# untitled.net
KiCad netlist of a schematic drawn in EAGLE
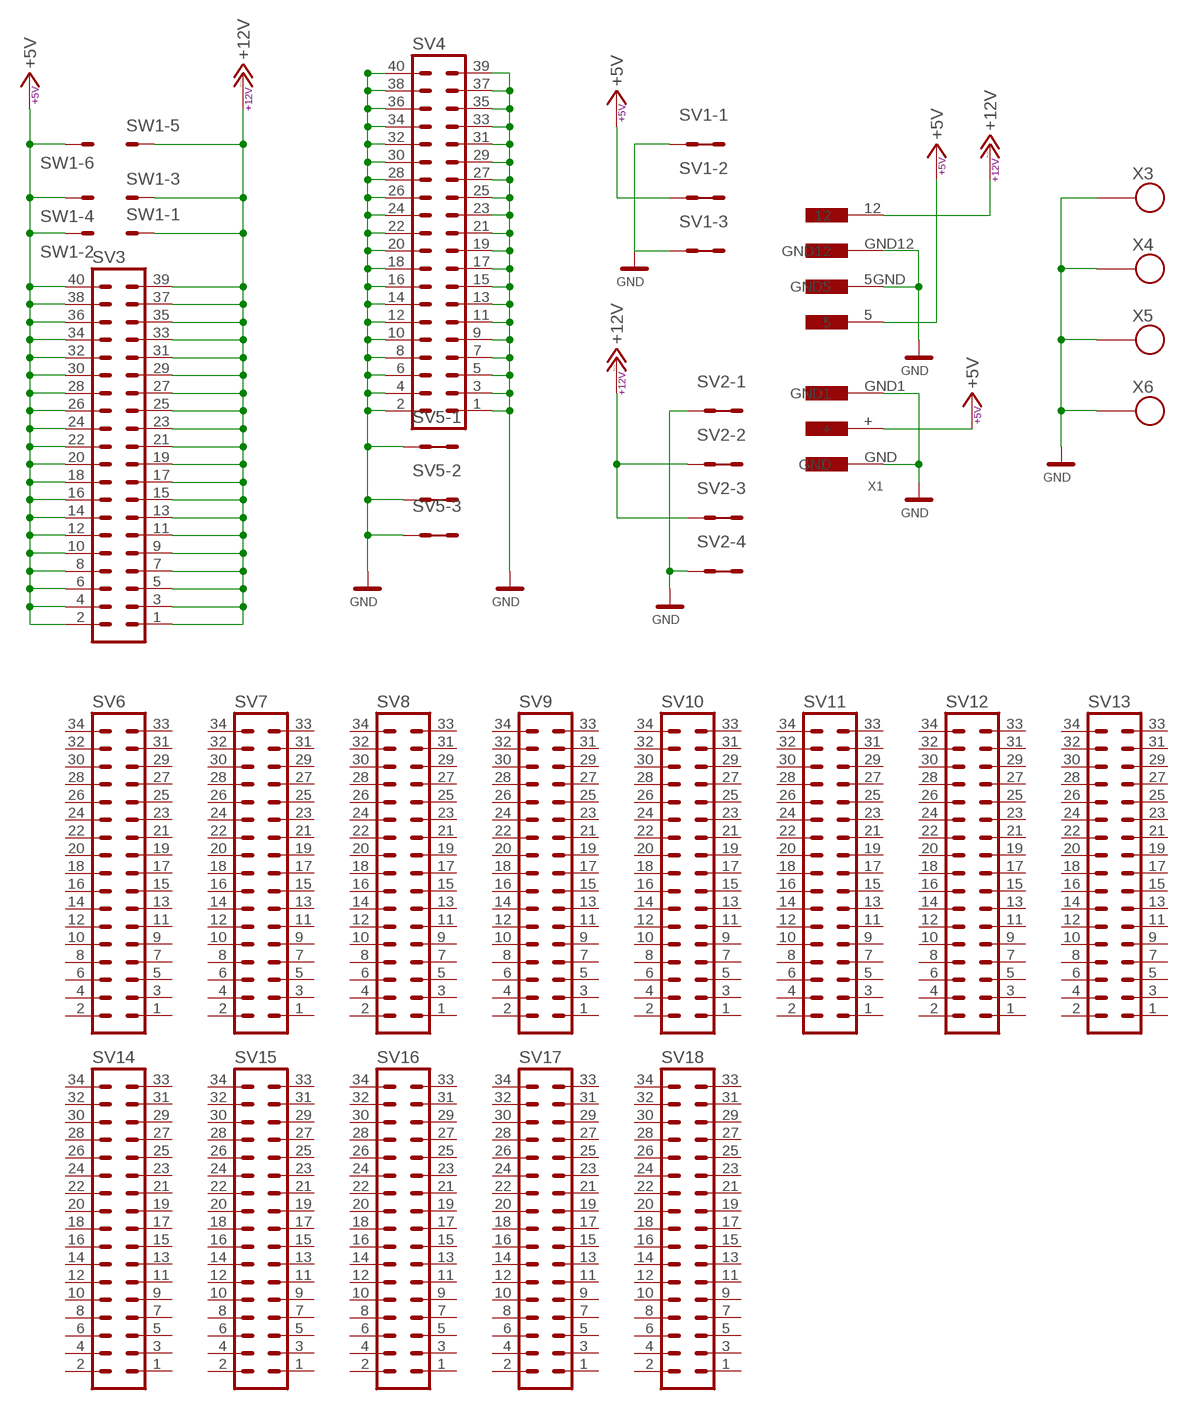
[diagram p0: schematic, sheet 1]

(export (version "E")
  (design (tool "Eeschema 10.0.6"))
  (components
    (comp (ref "SV1")
      (value "MA03-2")
      (footprint "eagle-import:MA03-2")
      (libsource (lib "eagle-import") (part "MA03-2"))
    )
    (comp (ref "SV2")
      (value "MA04-2")
      (footprint "eagle-import:MA04-2")
      (libsource (lib "eagle-import") (part "MA04-2"))
    )
    (comp (ref "SV3")
      (value "MA20-2")
      (footprint "eagle-import:MA20-2")
      (libsource (lib "eagle-import") (part "MA20-2"))
    )
    (comp (ref "SV4")
      (value "MA20-2")
      (footprint "eagle-import:MA20-2")
      (fields (field (name "OC_FARNELL") "unknown") (field (name "OC_NEWARK") "unknown"))
      (libsource (lib "eagle-import") (part "MA20-2"))
    )
    (comp (ref "SV5")
      (value "MA03-2")
      (footprint "eagle-import:MA03-2")
      (libsource (lib "eagle-import") (part "MA03-2"))
    )
    (comp (ref "SV6")
      (value "MA17-2")
      (footprint "eagle-import:MA17-2")
      (libsource (lib "eagle-import") (part "MA17-2"))
    )
    (comp (ref "SV7")
      (value "MA17-2")
      (footprint "eagle-import:MA17-2")
      (libsource (lib "eagle-import") (part "MA17-2"))
    )
    (comp (ref "SV8")
      (value "MA17-2")
      (footprint "eagle-import:MA17-2")
      (libsource (lib "eagle-import") (part "MA17-2"))
    )
    (comp (ref "SV9")
      (value "MA17-2")
      (footprint "eagle-import:MA17-2")
      (libsource (lib "eagle-import") (part "MA17-2"))
    )
    (comp (ref "SV10")
      (value "MA17-2")
      (footprint "eagle-import:MA17-2")
      (libsource (lib "eagle-import") (part "MA17-2"))
    )
    (comp (ref "SV11")
      (value "MA17-2")
      (footprint "eagle-import:MA17-2")
      (libsource (lib "eagle-import") (part "MA17-2"))
    )
    (comp (ref "SV12")
      (value "MA17-2")
      (footprint "eagle-import:MA17-2")
      (libsource (lib "eagle-import") (part "MA17-2"))
    )
    (comp (ref "SV13")
      (value "MA17-2")
      (footprint "eagle-import:MA17-2")
      (libsource (lib "eagle-import") (part "MA17-2"))
    )
    (comp (ref "SV14")
      (value "MA17-2")
      (footprint "eagle-import:MA17-2")
      (libsource (lib "eagle-import") (part "MA17-2"))
    )
    (comp (ref "SV15")
      (value "MA17-2")
      (footprint "eagle-import:MA17-2")
      (fields (field (name "OC_FARNELL") "unknown") (field (name "OC_NEWARK") "unknown"))
      (libsource (lib "eagle-import") (part "MA17-2"))
    )
    (comp (ref "SV16")
      (value "MA17-2")
      (footprint "eagle-import:MA17-2")
      (fields (field (name "OC_FARNELL") "unknown") (field (name "OC_NEWARK") "unknown"))
      (libsource (lib "eagle-import") (part "MA17-2"))
    )
    (comp (ref "SV17")
      (value "MA17-2")
      (footprint "eagle-import:MA17-2")
      (fields (field (name "OC_FARNELL") "unknown") (field (name "OC_NEWARK") "unknown"))
      (libsource (lib "eagle-import") (part "MA17-2"))
    )
    (comp (ref "SV18")
      (value "MA17-2")
      (footprint "eagle-import:MA17-2")
      (fields (field (name "OC_FARNELL") "unknown") (field (name "OC_NEWARK") "unknown"))
      (libsource (lib "eagle-import") (part "MA17-2"))
    )
    (comp (ref "SW1")
      (value "MA03-3")
      (footprint "eagle-import:MA03-2")
      (libsource (lib "eagle-import") (part "MA03-3"))
    )
    (comp (ref "X1")
      (value "KONEKTOR_DC_2.1MM")
      (footprint "eagle-import:KONEKTOR_DC_2.1MM")
      (libsource (lib "eagle-import") (part "KONEKTOR_DC_2.1MM"))
    )
    (comp (ref "X2")
      (value "POWER_HDD")
      (footprint "eagle-import:POWER_HDD")
      (libsource (lib "eagle-import") (part "POWER_HDD"))
    )
    (comp (ref "X3")
      (value "SROUB3M")
      (footprint "eagle-import:SROUB3M")
      (libsource (lib "eagle-import") (part "SROUB3M"))
    )
    (comp (ref "X4")
      (value "SROUB3M")
      (footprint "eagle-import:SROUB3M")
      (libsource (lib "eagle-import") (part "SROUB3M"))
    )
    (comp (ref "X5")
      (value "SROUB3M")
      (footprint "eagle-import:SROUB3M")
      (libsource (lib "eagle-import") (part "SROUB3M"))
    )
    (comp (ref "X6")
      (value "SROUB3M")
      (footprint "eagle-import:SROUB3M")
      (libsource (lib "eagle-import") (part "SROUB3M"))
    )
  )
  (nets
    (net (code "1") (name "+5V") (class "Default")
      (node (ref "SV1") (pin "3") (pinfunction "K_3") (pintype "passive"))
      (node (ref "SV1") (pin "4") (pinfunction "K_4") (pintype "passive"))
      (node (ref "SV3") (pin "10") (pinfunction "10_10") (pintype "passive"))
      (node (ref "SV3") (pin "12") (pinfunction "12_12") (pintype "passive"))
      (node (ref "SV3") (pin "14") (pinfunction "14_14") (pintype "passive"))
      (node (ref "SV3") (pin "16") (pinfunction "16_16") (pintype "passive"))
      (node (ref "SV3") (pin "18") (pinfunction "18_18") (pintype "passive"))
      (node (ref "SV3") (pin "2") (pinfunction "2_2") (pintype "passive"))
      (node (ref "SV3") (pin "20") (pinfunction "20_20") (pintype "passive"))
      (node (ref "SV3") (pin "22") (pinfunction "22_22") (pintype "passive"))
      (node (ref "SV3") (pin "24") (pinfunction "24_24") (pintype "passive"))
      (node (ref "SV3") (pin "26") (pinfunction "26_26") (pintype "passive"))
      (node (ref "SV3") (pin "28") (pinfunction "28_28") (pintype "passive"))
      (node (ref "SV3") (pin "30") (pinfunction "30_30") (pintype "passive"))
      (node (ref "SV3") (pin "32") (pinfunction "32_32") (pintype "passive"))
      (node (ref "SV3") (pin "34") (pinfunction "34_34") (pintype "passive"))
      (node (ref "SV3") (pin "36") (pinfunction "36_36") (pintype "passive"))
      (node (ref "SV3") (pin "38") (pinfunction "38_38") (pintype "passive"))
      (node (ref "SV3") (pin "4") (pinfunction "4_4") (pintype "passive"))
      (node (ref "SV3") (pin "40") (pinfunction "40_40") (pintype "passive"))
      (node (ref "SV3") (pin "6") (pinfunction "6_6") (pintype "passive"))
      (node (ref "SV3") (pin "8") (pinfunction "8_8") (pintype "passive"))
      (node (ref "SW1") (pin "2") (pinfunction "P$1_2") (pintype "passive"))
      (node (ref "SW1") (pin "4") (pinfunction "P$1_4") (pintype "passive"))
      (node (ref "SW1") (pin "6") (pinfunction "P$1_6") (pintype "passive"))
      (node (ref "X1") (pin "+") (pinfunction "+_+") (pintype "bidirectional"))
      (node (ref "X2") (pin "5") (pinfunction "5_5") (pintype "passive"))
    )
    (net (code "2") (name "+12V") (class "Default")
      (node (ref "SV2") (pin "3") (pinfunction "K_3") (pintype "passive"))
      (node (ref "SV2") (pin "4") (pinfunction "K_4") (pintype "passive"))
      (node (ref "SV2") (pin "5") (pinfunction "K_5") (pintype "passive"))
      (node (ref "SV2") (pin "6") (pinfunction "K_6") (pintype "passive"))
      (node (ref "SV3") (pin "1") (pinfunction "1_1") (pintype "passive"))
      (node (ref "SV3") (pin "11") (pinfunction "11_11") (pintype "passive"))
      (node (ref "SV3") (pin "13") (pinfunction "13_13") (pintype "passive"))
      (node (ref "SV3") (pin "15") (pinfunction "15_15") (pintype "passive"))
      (node (ref "SV3") (pin "17") (pinfunction "17_17") (pintype "passive"))
      (node (ref "SV3") (pin "19") (pinfunction "19_19") (pintype "passive"))
      (node (ref "SV3") (pin "21") (pinfunction "21_21") (pintype "passive"))
      (node (ref "SV3") (pin "23") (pinfunction "23_23") (pintype "passive"))
      (node (ref "SV3") (pin "25") (pinfunction "25_25") (pintype "passive"))
      (node (ref "SV3") (pin "27") (pinfunction "27_27") (pintype "passive"))
      (node (ref "SV3") (pin "29") (pinfunction "29_29") (pintype "passive"))
      (node (ref "SV3") (pin "3") (pinfunction "3_3") (pintype "passive"))
      (node (ref "SV3") (pin "31") (pinfunction "31_31") (pintype "passive"))
      (node (ref "SV3") (pin "33") (pinfunction "33_33") (pintype "passive"))
      (node (ref "SV3") (pin "35") (pinfunction "35_35") (pintype "passive"))
      (node (ref "SV3") (pin "37") (pinfunction "37_37") (pintype "passive"))
      (node (ref "SV3") (pin "39") (pinfunction "39_39") (pintype "passive"))
      (node (ref "SV3") (pin "5") (pinfunction "5_5") (pintype "passive"))
      (node (ref "SV3") (pin "7") (pinfunction "7_7") (pintype "passive"))
      (node (ref "SV3") (pin "9") (pinfunction "9_9") (pintype "passive"))
      (node (ref "SW1") (pin "1") (pinfunction "P$1_1") (pintype "passive"))
      (node (ref "SW1") (pin "3") (pinfunction "P$1_3") (pintype "passive"))
      (node (ref "SW1") (pin "5") (pinfunction "P$1_5") (pintype "passive"))
      (node (ref "X2") (pin "12") (pinfunction "12_12") (pintype "passive"))
    )
    (net (code "3") (name "GND") (class "Default")
      (node (ref "SV1") (pin "1") (pinfunction "K_1") (pintype "passive"))
      (node (ref "SV1") (pin "2") (pinfunction "K_2") (pintype "passive"))
      (node (ref "SV1") (pin "5") (pinfunction "K_5") (pintype "passive"))
      (node (ref "SV1") (pin "6") (pinfunction "K_6") (pintype "passive"))
      (node (ref "SV2") (pin "1") (pinfunction "K_1") (pintype "passive"))
      (node (ref "SV2") (pin "2") (pinfunction "K_2") (pintype "passive"))
      (node (ref "SV2") (pin "7") (pinfunction "K_7") (pintype "passive"))
      (node (ref "SV2") (pin "8") (pinfunction "K_8") (pintype "passive"))
      (node (ref "SV4") (pin "1") (pinfunction "1_1") (pintype "passive"))
      (node (ref "SV4") (pin "10") (pinfunction "10_10") (pintype "passive"))
      (node (ref "SV4") (pin "11") (pinfunction "11_11") (pintype "passive"))
      (node (ref "SV4") (pin "12") (pinfunction "12_12") (pintype "passive"))
      (node (ref "SV4") (pin "13") (pinfunction "13_13") (pintype "passive"))
      (node (ref "SV4") (pin "14") (pinfunction "14_14") (pintype "passive"))
      (node (ref "SV4") (pin "15") (pinfunction "15_15") (pintype "passive"))
      (node (ref "SV4") (pin "16") (pinfunction "16_16") (pintype "passive"))
      (node (ref "SV4") (pin "17") (pinfunction "17_17") (pintype "passive"))
      (node (ref "SV4") (pin "18") (pinfunction "18_18") (pintype "passive"))
      (node (ref "SV4") (pin "19") (pinfunction "19_19") (pintype "passive"))
      (node (ref "SV4") (pin "2") (pinfunction "2_2") (pintype "passive"))
      (node (ref "SV4") (pin "20") (pinfunction "20_20") (pintype "passive"))
      (node (ref "SV4") (pin "21") (pinfunction "21_21") (pintype "passive"))
      (node (ref "SV4") (pin "22") (pinfunction "22_22") (pintype "passive"))
      (node (ref "SV4") (pin "23") (pinfunction "23_23") (pintype "passive"))
      (node (ref "SV4") (pin "24") (pinfunction "24_24") (pintype "passive"))
      (node (ref "SV4") (pin "25") (pinfunction "25_25") (pintype "passive"))
      (node (ref "SV4") (pin "26") (pinfunction "26_26") (pintype "passive"))
      (node (ref "SV4") (pin "27") (pinfunction "27_27") (pintype "passive"))
      (node (ref "SV4") (pin "28") (pinfunction "28_28") (pintype "passive"))
      (node (ref "SV4") (pin "29") (pinfunction "29_29") (pintype "passive"))
      (node (ref "SV4") (pin "3") (pinfunction "3_3") (pintype "passive"))
      (node (ref "SV4") (pin "30") (pinfunction "30_30") (pintype "passive"))
      (node (ref "SV4") (pin "31") (pinfunction "31_31") (pintype "passive"))
      (node (ref "SV4") (pin "32") (pinfunction "32_32") (pintype "passive"))
      (node (ref "SV4") (pin "33") (pinfunction "33_33") (pintype "passive"))
      (node (ref "SV4") (pin "34") (pinfunction "34_34") (pintype "passive"))
      (node (ref "SV4") (pin "35") (pinfunction "35_35") (pintype "passive"))
      (node (ref "SV4") (pin "36") (pinfunction "36_36") (pintype "passive"))
      (node (ref "SV4") (pin "37") (pinfunction "37_37") (pintype "passive"))
      (node (ref "SV4") (pin "38") (pinfunction "38_38") (pintype "passive"))
      (node (ref "SV4") (pin "39") (pinfunction "39_39") (pintype "passive"))
      (node (ref "SV4") (pin "4") (pinfunction "4_4") (pintype "passive"))
      (node (ref "SV4") (pin "40") (pinfunction "40_40") (pintype "passive"))
      (node (ref "SV4") (pin "5") (pinfunction "5_5") (pintype "passive"))
      (node (ref "SV4") (pin "6") (pinfunction "6_6") (pintype "passive"))
      (node (ref "SV4") (pin "7") (pinfunction "7_7") (pintype "passive"))
      (node (ref "SV4") (pin "8") (pinfunction "8_8") (pintype "passive"))
      (node (ref "SV4") (pin "9") (pinfunction "9_9") (pintype "passive"))
      (node (ref "SV5") (pin "1") (pinfunction "K_1") (pintype "passive"))
      (node (ref "SV5") (pin "2") (pinfunction "K_2") (pintype "passive"))
      (node (ref "SV5") (pin "3") (pinfunction "K_3") (pintype "passive"))
      (node (ref "SV5") (pin "4") (pinfunction "K_4") (pintype "passive"))
      (node (ref "SV5") (pin "5") (pinfunction "K_5") (pintype "passive"))
      (node (ref "SV5") (pin "6") (pinfunction "K_6") (pintype "passive"))
      (node (ref "X1") (pin "GND") (pinfunction "GND_GND") (pintype "bidirectional"))
      (node (ref "X1") (pin "GND1") (pinfunction "GND1_GND1") (pintype "bidirectional"))
      (node (ref "X2") (pin "5GND") (pinfunction "GND5_5GND") (pintype "passive"))
      (node (ref "X2") (pin "GND12") (pinfunction "GND12_GND12") (pintype "passive"))
      (node (ref "X3") (pin "P$1") (pinfunction "P$1_P$1") (pintype "bidirectional"))
      (node (ref "X4") (pin "P$1") (pinfunction "P$1_P$1") (pintype "bidirectional"))
      (node (ref "X5") (pin "P$1") (pinfunction "P$1_P$1") (pintype "bidirectional"))
      (node (ref "X6") (pin "P$1") (pinfunction "P$1_P$1") (pintype "bidirectional"))
    )
    (net (code "4") (name "unconnected-(SV6-Pad1)") (class "Default")
      (node (ref "SV6") (pin "1") (pinfunction "1_1") (pintype "passive"))
    )
    (net (code "5") (name "unconnected-(SV6-Pad2)") (class "Default")
      (node (ref "SV6") (pin "2") (pinfunction "2_2") (pintype "passive"))
    )
    (net (code "6") (name "unconnected-(SV6-Pad3)") (class "Default")
      (node (ref "SV6") (pin "3") (pinfunction "3_3") (pintype "passive"))
    )
    (net (code "7") (name "unconnected-(SV6-Pad4)") (class "Default")
      (node (ref "SV6") (pin "4") (pinfunction "4_4") (pintype "passive"))
    )
    (net (code "8") (name "unconnected-(SV6-Pad5)") (class "Default")
      (node (ref "SV6") (pin "5") (pinfunction "5_5") (pintype "passive"))
    )
    (net (code "9") (name "unconnected-(SV6-Pad6)") (class "Default")
      (node (ref "SV6") (pin "6") (pinfunction "6_6") (pintype "passive"))
    )
    (net (code "10") (name "unconnected-(SV6-Pad7)") (class "Default")
      (node (ref "SV6") (pin "7") (pinfunction "7_7") (pintype "passive"))
    )
    (net (code "11") (name "unconnected-(SV6-Pad8)") (class "Default")
      (node (ref "SV6") (pin "8") (pinfunction "8_8") (pintype "passive"))
    )
    (net (code "12") (name "unconnected-(SV6-Pad9)") (class "Default")
      (node (ref "SV6") (pin "9") (pinfunction "9_9") (pintype "passive"))
    )
    (net (code "13") (name "unconnected-(SV6-Pad10)") (class "Default")
      (node (ref "SV6") (pin "10") (pinfunction "10_10") (pintype "passive"))
    )
    (net (code "14") (name "unconnected-(SV6-Pad11)") (class "Default")
      (node (ref "SV6") (pin "11") (pinfunction "11_11") (pintype "passive"))
    )
    (net (code "15") (name "unconnected-(SV6-Pad12)") (class "Default")
      (node (ref "SV6") (pin "12") (pinfunction "12_12") (pintype "passive"))
    )
    (net (code "16") (name "unconnected-(SV6-Pad13)") (class "Default")
      (node (ref "SV6") (pin "13") (pinfunction "13_13") (pintype "passive"))
    )
    (net (code "17") (name "unconnected-(SV6-Pad14)") (class "Default")
      (node (ref "SV6") (pin "14") (pinfunction "14_14") (pintype "passive"))
    )
    (net (code "18") (name "unconnected-(SV6-Pad15)") (class "Default")
      (node (ref "SV6") (pin "15") (pinfunction "15_15") (pintype "passive"))
    )
    (net (code "19") (name "unconnected-(SV6-Pad16)") (class "Default")
      (node (ref "SV6") (pin "16") (pinfunction "16_16") (pintype "passive"))
    )
    (net (code "20") (name "unconnected-(SV6-Pad17)") (class "Default")
      (node (ref "SV6") (pin "17") (pinfunction "17_17") (pintype "passive"))
    )
    (net (code "21") (name "unconnected-(SV6-Pad18)") (class "Default")
      (node (ref "SV6") (pin "18") (pinfunction "18_18") (pintype "passive"))
    )
    (net (code "22") (name "unconnected-(SV6-Pad19)") (class "Default")
      (node (ref "SV6") (pin "19") (pinfunction "19_19") (pintype "passive"))
    )
    (net (code "23") (name "unconnected-(SV6-Pad20)") (class "Default")
      (node (ref "SV6") (pin "20") (pinfunction "20_20") (pintype "passive"))
    )
    (net (code "24") (name "unconnected-(SV6-Pad21)") (class "Default")
      (node (ref "SV6") (pin "21") (pinfunction "21_21") (pintype "passive"))
    )
    (net (code "25") (name "unconnected-(SV6-Pad22)") (class "Default")
      (node (ref "SV6") (pin "22") (pinfunction "22_22") (pintype "passive"))
    )
    (net (code "26") (name "unconnected-(SV6-Pad23)") (class "Default")
      (node (ref "SV6") (pin "23") (pinfunction "23_23") (pintype "passive"))
    )
    (net (code "27") (name "unconnected-(SV6-Pad24)") (class "Default")
      (node (ref "SV6") (pin "24") (pinfunction "24_24") (pintype "passive"))
    )
    (net (code "28") (name "unconnected-(SV6-Pad25)") (class "Default")
      (node (ref "SV6") (pin "25") (pinfunction "25_25") (pintype "passive"))
    )
    (net (code "29") (name "unconnected-(SV6-Pad26)") (class "Default")
      (node (ref "SV6") (pin "26") (pinfunction "26_26") (pintype "passive"))
    )
    (net (code "30") (name "unconnected-(SV6-Pad27)") (class "Default")
      (node (ref "SV6") (pin "27") (pinfunction "27_27") (pintype "passive"))
    )
    (net (code "31") (name "unconnected-(SV6-Pad28)") (class "Default")
      (node (ref "SV6") (pin "28") (pinfunction "28_28") (pintype "passive"))
    )
    (net (code "32") (name "unconnected-(SV6-Pad29)") (class "Default")
      (node (ref "SV6") (pin "29") (pinfunction "29_29") (pintype "passive"))
    )
    (net (code "33") (name "unconnected-(SV6-Pad30)") (class "Default")
      (node (ref "SV6") (pin "30") (pinfunction "30_30") (pintype "passive"))
    )
    (net (code "34") (name "unconnected-(SV6-Pad31)") (class "Default")
      (node (ref "SV6") (pin "31") (pinfunction "31_31") (pintype "passive"))
    )
    (net (code "35") (name "unconnected-(SV6-Pad32)") (class "Default")
      (node (ref "SV6") (pin "32") (pinfunction "32_32") (pintype "passive"))
    )
    (net (code "36") (name "unconnected-(SV6-Pad33)") (class "Default")
      (node (ref "SV6") (pin "33") (pinfunction "33_33") (pintype "passive"))
    )
    (net (code "37") (name "unconnected-(SV6-Pad34)") (class "Default")
      (node (ref "SV6") (pin "34") (pinfunction "34_34") (pintype "passive"))
    )
    (net (code "38") (name "unconnected-(SV7-Pad1)") (class "Default")
      (node (ref "SV7") (pin "1") (pinfunction "1_1") (pintype "passive"))
    )
    (net (code "39") (name "unconnected-(SV7-Pad2)") (class "Default")
      (node (ref "SV7") (pin "2") (pinfunction "2_2") (pintype "passive"))
    )
    (net (code "40") (name "unconnected-(SV7-Pad3)") (class "Default")
      (node (ref "SV7") (pin "3") (pinfunction "3_3") (pintype "passive"))
    )
    (net (code "41") (name "unconnected-(SV7-Pad4)") (class "Default")
      (node (ref "SV7") (pin "4") (pinfunction "4_4") (pintype "passive"))
    )
    (net (code "42") (name "unconnected-(SV7-Pad5)") (class "Default")
      (node (ref "SV7") (pin "5") (pinfunction "5_5") (pintype "passive"))
    )
    (net (code "43") (name "unconnected-(SV7-Pad6)") (class "Default")
      (node (ref "SV7") (pin "6") (pinfunction "6_6") (pintype "passive"))
    )
    (net (code "44") (name "unconnected-(SV7-Pad7)") (class "Default")
      (node (ref "SV7") (pin "7") (pinfunction "7_7") (pintype "passive"))
    )
    (net (code "45") (name "unconnected-(SV7-Pad8)") (class "Default")
      (node (ref "SV7") (pin "8") (pinfunction "8_8") (pintype "passive"))
    )
    (net (code "46") (name "unconnected-(SV7-Pad9)") (class "Default")
      (node (ref "SV7") (pin "9") (pinfunction "9_9") (pintype "passive"))
    )
    (net (code "47") (name "unconnected-(SV7-Pad10)") (class "Default")
      (node (ref "SV7") (pin "10") (pinfunction "10_10") (pintype "passive"))
    )
    (net (code "48") (name "unconnected-(SV7-Pad11)") (class "Default")
      (node (ref "SV7") (pin "11") (pinfunction "11_11") (pintype "passive"))
    )
    (net (code "49") (name "unconnected-(SV7-Pad12)") (class "Default")
      (node (ref "SV7") (pin "12") (pinfunction "12_12") (pintype "passive"))
    )
    (net (code "50") (name "unconnected-(SV7-Pad13)") (class "Default")
      (node (ref "SV7") (pin "13") (pinfunction "13_13") (pintype "passive"))
    )
    (net (code "51") (name "unconnected-(SV7-Pad14)") (class "Default")
      (node (ref "SV7") (pin "14") (pinfunction "14_14") (pintype "passive"))
    )
    (net (code "52") (name "unconnected-(SV7-Pad15)") (class "Default")
      (node (ref "SV7") (pin "15") (pinfunction "15_15") (pintype "passive"))
    )
    (net (code "53") (name "unconnected-(SV7-Pad16)") (class "Default")
      (node (ref "SV7") (pin "16") (pinfunction "16_16") (pintype "passive"))
    )
    (net (code "54") (name "unconnected-(SV7-Pad17)") (class "Default")
      (node (ref "SV7") (pin "17") (pinfunction "17_17") (pintype "passive"))
    )
    (net (code "55") (name "unconnected-(SV7-Pad18)") (class "Default")
      (node (ref "SV7") (pin "18") (pinfunction "18_18") (pintype "passive"))
    )
    (net (code "56") (name "unconnected-(SV7-Pad19)") (class "Default")
      (node (ref "SV7") (pin "19") (pinfunction "19_19") (pintype "passive"))
    )
    (net (code "57") (name "unconnected-(SV7-Pad20)") (class "Default")
      (node (ref "SV7") (pin "20") (pinfunction "20_20") (pintype "passive"))
    )
    (net (code "58") (name "unconnected-(SV7-Pad21)") (class "Default")
      (node (ref "SV7") (pin "21") (pinfunction "21_21") (pintype "passive"))
    )
    (net (code "59") (name "unconnected-(SV7-Pad22)") (class "Default")
      (node (ref "SV7") (pin "22") (pinfunction "22_22") (pintype "passive"))
    )
    (net (code "60") (name "unconnected-(SV7-Pad23)") (class "Default")
      (node (ref "SV7") (pin "23") (pinfunction "23_23") (pintype "passive"))
    )
    (net (code "61") (name "unconnected-(SV7-Pad24)") (class "Default")
      (node (ref "SV7") (pin "24") (pinfunction "24_24") (pintype "passive"))
    )
    (net (code "62") (name "unconnected-(SV7-Pad25)") (class "Default")
      (node (ref "SV7") (pin "25") (pinfunction "25_25") (pintype "passive"))
    )
    (net (code "63") (name "unconnected-(SV7-Pad26)") (class "Default")
      (node (ref "SV7") (pin "26") (pinfunction "26_26") (pintype "passive"))
    )
    (net (code "64") (name "unconnected-(SV7-Pad27)") (class "Default")
      (node (ref "SV7") (pin "27") (pinfunction "27_27") (pintype "passive"))
    )
    (net (code "65") (name "unconnected-(SV7-Pad28)") (class "Default")
      (node (ref "SV7") (pin "28") (pinfunction "28_28") (pintype "passive"))
    )
    (net (code "66") (name "unconnected-(SV7-Pad29)") (class "Default")
      (node (ref "SV7") (pin "29") (pinfunction "29_29") (pintype "passive"))
    )
    (net (code "67") (name "unconnected-(SV7-Pad30)") (class "Default")
      (node (ref "SV7") (pin "30") (pinfunction "30_30") (pintype "passive"))
    )
    (net (code "68") (name "unconnected-(SV7-Pad31)") (class "Default")
      (node (ref "SV7") (pin "31") (pinfunction "31_31") (pintype "passive"))
    )
    (net (code "69") (name "unconnected-(SV7-Pad32)") (class "Default")
      (node (ref "SV7") (pin "32") (pinfunction "32_32") (pintype "passive"))
    )
    (net (code "70") (name "unconnected-(SV7-Pad33)") (class "Default")
      (node (ref "SV7") (pin "33") (pinfunction "33_33") (pintype "passive"))
    )
    (net (code "71") (name "unconnected-(SV7-Pad34)") (class "Default")
      (node (ref "SV7") (pin "34") (pinfunction "34_34") (pintype "passive"))
    )
    (net (code "72") (name "unconnected-(SV8-Pad1)") (class "Default")
      (node (ref "SV8") (pin "1") (pinfunction "1_1") (pintype "passive"))
    )
    (net (code "73") (name "unconnected-(SV8-Pad2)") (class "Default")
      (node (ref "SV8") (pin "2") (pinfunction "2_2") (pintype "passive"))
    )
    (net (code "74") (name "unconnected-(SV8-Pad3)") (class "Default")
      (node (ref "SV8") (pin "3") (pinfunction "3_3") (pintype "passive"))
    )
    (net (code "75") (name "unconnected-(SV8-Pad4)") (class "Default")
      (node (ref "SV8") (pin "4") (pinfunction "4_4") (pintype "passive"))
    )
    (net (code "76") (name "unconnected-(SV8-Pad5)") (class "Default")
      (node (ref "SV8") (pin "5") (pinfunction "5_5") (pintype "passive"))
    )
    (net (code "77") (name "unconnected-(SV8-Pad6)") (class "Default")
      (node (ref "SV8") (pin "6") (pinfunction "6_6") (pintype "passive"))
    )
    (net (code "78") (name "unconnected-(SV8-Pad7)") (class "Default")
      (node (ref "SV8") (pin "7") (pinfunction "7_7") (pintype "passive"))
    )
    (net (code "79") (name "unconnected-(SV8-Pad8)") (class "Default")
      (node (ref "SV8") (pin "8") (pinfunction "8_8") (pintype "passive"))
    )
    (net (code "80") (name "unconnected-(SV8-Pad9)") (class "Default")
      (node (ref "SV8") (pin "9") (pinfunction "9_9") (pintype "passive"))
    )
    (net (code "81") (name "unconnected-(SV8-Pad10)") (class "Default")
      (node (ref "SV8") (pin "10") (pinfunction "10_10") (pintype "passive"))
    )
    (net (code "82") (name "unconnected-(SV8-Pad11)") (class "Default")
      (node (ref "SV8") (pin "11") (pinfunction "11_11") (pintype "passive"))
    )
    (net (code "83") (name "unconnected-(SV8-Pad12)") (class "Default")
      (node (ref "SV8") (pin "12") (pinfunction "12_12") (pintype "passive"))
    )
    (net (code "84") (name "unconnected-(SV8-Pad13)") (class "Default")
      (node (ref "SV8") (pin "13") (pinfunction "13_13") (pintype "passive"))
    )
    (net (code "85") (name "unconnected-(SV8-Pad14)") (class "Default")
      (node (ref "SV8") (pin "14") (pinfunction "14_14") (pintype "passive"))
    )
    (net (code "86") (name "unconnected-(SV8-Pad15)") (class "Default")
      (node (ref "SV8") (pin "15") (pinfunction "15_15") (pintype "passive"))
    )
    (net (code "87") (name "unconnected-(SV8-Pad16)") (class "Default")
      (node (ref "SV8") (pin "16") (pinfunction "16_16") (pintype "passive"))
    )
    (net (code "88") (name "unconnected-(SV8-Pad17)") (class "Default")
      (node (ref "SV8") (pin "17") (pinfunction "17_17") (pintype "passive"))
    )
    (net (code "89") (name "unconnected-(SV8-Pad18)") (class "Default")
      (node (ref "SV8") (pin "18") (pinfunction "18_18") (pintype "passive"))
    )
    (net (code "90") (name "unconnected-(SV8-Pad19)") (class "Default")
      (node (ref "SV8") (pin "19") (pinfunction "19_19") (pintype "passive"))
    )
    (net (code "91") (name "unconnected-(SV8-Pad20)") (class "Default")
      (node (ref "SV8") (pin "20") (pinfunction "20_20") (pintype "passive"))
    )
    (net (code "92") (name "unconnected-(SV8-Pad21)") (class "Default")
      (node (ref "SV8") (pin "21") (pinfunction "21_21") (pintype "passive"))
    )
    (net (code "93") (name "unconnected-(SV8-Pad22)") (class "Default")
      (node (ref "SV8") (pin "22") (pinfunction "22_22") (pintype "passive"))
    )
    (net (code "94") (name "unconnected-(SV8-Pad23)") (class "Default")
      (node (ref "SV8") (pin "23") (pinfunction "23_23") (pintype "passive"))
    )
    (net (code "95") (name "unconnected-(SV8-Pad24)") (class "Default")
      (node (ref "SV8") (pin "24") (pinfunction "24_24") (pintype "passive"))
    )
    (net (code "96") (name "unconnected-(SV8-Pad25)") (class "Default")
      (node (ref "SV8") (pin "25") (pinfunction "25_25") (pintype "passive"))
    )
    (net (code "97") (name "unconnected-(SV8-Pad26)") (class "Default")
      (node (ref "SV8") (pin "26") (pinfunction "26_26") (pintype "passive"))
    )
    (net (code "98") (name "unconnected-(SV8-Pad27)") (class "Default")
      (node (ref "SV8") (pin "27") (pinfunction "27_27") (pintype "passive"))
    )
    (net (code "99") (name "unconnected-(SV8-Pad28)") (class "Default")
      (node (ref "SV8") (pin "28") (pinfunction "28_28") (pintype "passive"))
    )
    (net (code "100") (name "unconnected-(SV8-Pad29)") (class "Default")
      (node (ref "SV8") (pin "29") (pinfunction "29_29") (pintype "passive"))
    )
    (net (code "101") (name "unconnected-(SV8-Pad30)") (class "Default")
      (node (ref "SV8") (pin "30") (pinfunction "30_30") (pintype "passive"))
    )
    (net (code "102") (name "unconnected-(SV8-Pad31)") (class "Default")
      (node (ref "SV8") (pin "31") (pinfunction "31_31") (pintype "passive"))
    )
    (net (code "103") (name "unconnected-(SV8-Pad32)") (class "Default")
      (node (ref "SV8") (pin "32") (pinfunction "32_32") (pintype "passive"))
    )
    (net (code "104") (name "unconnected-(SV8-Pad33)") (class "Default")
      (node (ref "SV8") (pin "33") (pinfunction "33_33") (pintype "passive"))
    )
    (net (code "105") (name "unconnected-(SV8-Pad34)") (class "Default")
      (node (ref "SV8") (pin "34") (pinfunction "34_34") (pintype "passive"))
    )
    (net (code "106") (name "unconnected-(SV9-Pad1)") (class "Default")
      (node (ref "SV9") (pin "1") (pinfunction "1_1") (pintype "passive"))
    )
    (net (code "107") (name "unconnected-(SV9-Pad2)") (class "Default")
      (node (ref "SV9") (pin "2") (pinfunction "2_2") (pintype "passive"))
    )
    (net (code "108") (name "unconnected-(SV9-Pad3)") (class "Default")
      (node (ref "SV9") (pin "3") (pinfunction "3_3") (pintype "passive"))
    )
    (net (code "109") (name "unconnected-(SV9-Pad4)") (class "Default")
      (node (ref "SV9") (pin "4") (pinfunction "4_4") (pintype "passive"))
    )
    (net (code "110") (name "unconnected-(SV9-Pad5)") (class "Default")
      (node (ref "SV9") (pin "5") (pinfunction "5_5") (pintype "passive"))
    )
    (net (code "111") (name "unconnected-(SV9-Pad6)") (class "Default")
      (node (ref "SV9") (pin "6") (pinfunction "6_6") (pintype "passive"))
    )
    (net (code "112") (name "unconnected-(SV9-Pad7)") (class "Default")
      (node (ref "SV9") (pin "7") (pinfunction "7_7") (pintype "passive"))
    )
    (net (code "113") (name "unconnected-(SV9-Pad8)") (class "Default")
      (node (ref "SV9") (pin "8") (pinfunction "8_8") (pintype "passive"))
    )
    (net (code "114") (name "unconnected-(SV9-Pad9)") (class "Default")
      (node (ref "SV9") (pin "9") (pinfunction "9_9") (pintype "passive"))
    )
    (net (code "115") (name "unconnected-(SV9-Pad10)") (class "Default")
      (node (ref "SV9") (pin "10") (pinfunction "10_10") (pintype "passive"))
    )
    (net (code "116") (name "unconnected-(SV9-Pad11)") (class "Default")
      (node (ref "SV9") (pin "11") (pinfunction "11_11") (pintype "passive"))
    )
    (net (code "117") (name "unconnected-(SV9-Pad12)") (class "Default")
      (node (ref "SV9") (pin "12") (pinfunction "12_12") (pintype "passive"))
    )
    (net (code "118") (name "unconnected-(SV9-Pad13)") (class "Default")
      (node (ref "SV9") (pin "13") (pinfunction "13_13") (pintype "passive"))
    )
    (net (code "119") (name "unconnected-(SV9-Pad14)") (class "Default")
      (node (ref "SV9") (pin "14") (pinfunction "14_14") (pintype "passive"))
    )
    (net (code "120") (name "unconnected-(SV9-Pad15)") (class "Default")
      (node (ref "SV9") (pin "15") (pinfunction "15_15") (pintype "passive"))
    )
    (net (code "121") (name "unconnected-(SV9-Pad16)") (class "Default")
      (node (ref "SV9") (pin "16") (pinfunction "16_16") (pintype "passive"))
    )
    (net (code "122") (name "unconnected-(SV9-Pad17)") (class "Default")
      (node (ref "SV9") (pin "17") (pinfunction "17_17") (pintype "passive"))
    )
    (net (code "123") (name "unconnected-(SV9-Pad18)") (class "Default")
      (node (ref "SV9") (pin "18") (pinfunction "18_18") (pintype "passive"))
    )
    (net (code "124") (name "unconnected-(SV9-Pad19)") (class "Default")
      (node (ref "SV9") (pin "19") (pinfunction "19_19") (pintype "passive"))
    )
    (net (code "125") (name "unconnected-(SV9-Pad20)") (class "Default")
      (node (ref "SV9") (pin "20") (pinfunction "20_20") (pintype "passive"))
    )
    (net (code "126") (name "unconnected-(SV9-Pad21)") (class "Default")
      (node (ref "SV9") (pin "21") (pinfunction "21_21") (pintype "passive"))
    )
    (net (code "127") (name "unconnected-(SV9-Pad22)") (class "Default")
      (node (ref "SV9") (pin "22") (pinfunction "22_22") (pintype "passive"))
    )
    (net (code "128") (name "unconnected-(SV9-Pad23)") (class "Default")
      (node (ref "SV9") (pin "23") (pinfunction "23_23") (pintype "passive"))
    )
    (net (code "129") (name "unconnected-(SV9-Pad24)") (class "Default")
      (node (ref "SV9") (pin "24") (pinfunction "24_24") (pintype "passive"))
    )
    (net (code "130") (name "unconnected-(SV9-Pad25)") (class "Default")
      (node (ref "SV9") (pin "25") (pinfunction "25_25") (pintype "passive"))
    )
    (net (code "131") (name "unconnected-(SV9-Pad26)") (class "Default")
      (node (ref "SV9") (pin "26") (pinfunction "26_26") (pintype "passive"))
    )
    (net (code "132") (name "unconnected-(SV9-Pad27)") (class "Default")
      (node (ref "SV9") (pin "27") (pinfunction "27_27") (pintype "passive"))
    )
    (net (code "133") (name "unconnected-(SV9-Pad28)") (class "Default")
      (node (ref "SV9") (pin "28") (pinfunction "28_28") (pintype "passive"))
    )
    (net (code "134") (name "unconnected-(SV9-Pad29)") (class "Default")
      (node (ref "SV9") (pin "29") (pinfunction "29_29") (pintype "passive"))
    )
    (net (code "135") (name "unconnected-(SV9-Pad30)") (class "Default")
      (node (ref "SV9") (pin "30") (pinfunction "30_30") (pintype "passive"))
    )
    (net (code "136") (name "unconnected-(SV9-Pad31)") (class "Default")
      (node (ref "SV9") (pin "31") (pinfunction "31_31") (pintype "passive"))
    )
    (net (code "137") (name "unconnected-(SV9-Pad32)") (class "Default")
      (node (ref "SV9") (pin "32") (pinfunction "32_32") (pintype "passive"))
    )
    (net (code "138") (name "unconnected-(SV9-Pad33)") (class "Default")
      (node (ref "SV9") (pin "33") (pinfunction "33_33") (pintype "passive"))
    )
    (net (code "139") (name "unconnected-(SV9-Pad34)") (class "Default")
      (node (ref "SV9") (pin "34") (pinfunction "34_34") (pintype "passive"))
    )
    (net (code "140") (name "unconnected-(SV10-Pad1)") (class "Default")
      (node (ref "SV10") (pin "1") (pinfunction "1_1") (pintype "passive"))
    )
    (net (code "141") (name "unconnected-(SV10-Pad2)") (class "Default")
      (node (ref "SV10") (pin "2") (pinfunction "2_2") (pintype "passive"))
    )
    (net (code "142") (name "unconnected-(SV10-Pad3)") (class "Default")
      (node (ref "SV10") (pin "3") (pinfunction "3_3") (pintype "passive"))
    )
    (net (code "143") (name "unconnected-(SV10-Pad4)") (class "Default")
      (node (ref "SV10") (pin "4") (pinfunction "4_4") (pintype "passive"))
    )
    (net (code "144") (name "unconnected-(SV10-Pad5)") (class "Default")
      (node (ref "SV10") (pin "5") (pinfunction "5_5") (pintype "passive"))
    )
    (net (code "145") (name "unconnected-(SV10-Pad6)") (class "Default")
      (node (ref "SV10") (pin "6") (pinfunction "6_6") (pintype "passive"))
    )
    (net (code "146") (name "unconnected-(SV10-Pad7)") (class "Default")
      (node (ref "SV10") (pin "7") (pinfunction "7_7") (pintype "passive"))
    )
    (net (code "147") (name "unconnected-(SV10-Pad8)") (class "Default")
      (node (ref "SV10") (pin "8") (pinfunction "8_8") (pintype "passive"))
    )
    (net (code "148") (name "unconnected-(SV10-Pad9)") (class "Default")
      (node (ref "SV10") (pin "9") (pinfunction "9_9") (pintype "passive"))
    )
    (net (code "149") (name "unconnected-(SV10-Pad10)") (class "Default")
      (node (ref "SV10") (pin "10") (pinfunction "10_10") (pintype "passive"))
    )
    (net (code "150") (name "unconnected-(SV10-Pad11)") (class "Default")
      (node (ref "SV10") (pin "11") (pinfunction "11_11") (pintype "passive"))
    )
    (net (code "151") (name "unconnected-(SV10-Pad12)") (class "Default")
      (node (ref "SV10") (pin "12") (pinfunction "12_12") (pintype "passive"))
    )
    (net (code "152") (name "unconnected-(SV10-Pad13)") (class "Default")
      (node (ref "SV10") (pin "13") (pinfunction "13_13") (pintype "passive"))
    )
    (net (code "153") (name "unconnected-(SV10-Pad14)") (class "Default")
      (node (ref "SV10") (pin "14") (pinfunction "14_14") (pintype "passive"))
    )
    (net (code "154") (name "unconnected-(SV10-Pad15)") (class "Default")
      (node (ref "SV10") (pin "15") (pinfunction "15_15") (pintype "passive"))
    )
    (net (code "155") (name "unconnected-(SV10-Pad16)") (class "Default")
      (node (ref "SV10") (pin "16") (pinfunction "16_16") (pintype "passive"))
    )
    (net (code "156") (name "unconnected-(SV10-Pad17)") (class "Default")
      (node (ref "SV10") (pin "17") (pinfunction "17_17") (pintype "passive"))
    )
    (net (code "157") (name "unconnected-(SV10-Pad18)") (class "Default")
      (node (ref "SV10") (pin "18") (pinfunction "18_18") (pintype "passive"))
    )
    (net (code "158") (name "unconnected-(SV10-Pad19)") (class "Default")
      (node (ref "SV10") (pin "19") (pinfunction "19_19") (pintype "passive"))
    )
    (net (code "159") (name "unconnected-(SV10-Pad20)") (class "Default")
      (node (ref "SV10") (pin "20") (pinfunction "20_20") (pintype "passive"))
    )
    (net (code "160") (name "unconnected-(SV10-Pad21)") (class "Default")
      (node (ref "SV10") (pin "21") (pinfunction "21_21") (pintype "passive"))
    )
    (net (code "161") (name "unconnected-(SV10-Pad22)") (class "Default")
      (node (ref "SV10") (pin "22") (pinfunction "22_22") (pintype "passive"))
    )
    (net (code "162") (name "unconnected-(SV10-Pad23)") (class "Default")
      (node (ref "SV10") (pin "23") (pinfunction "23_23") (pintype "passive"))
    )
    (net (code "163") (name "unconnected-(SV10-Pad24)") (class "Default")
      (node (ref "SV10") (pin "24") (pinfunction "24_24") (pintype "passive"))
    )
    (net (code "164") (name "unconnected-(SV10-Pad25)") (class "Default")
      (node (ref "SV10") (pin "25") (pinfunction "25_25") (pintype "passive"))
    )
    (net (code "165") (name "unconnected-(SV10-Pad26)") (class "Default")
      (node (ref "SV10") (pin "26") (pinfunction "26_26") (pintype "passive"))
    )
    (net (code "166") (name "unconnected-(SV10-Pad27)") (class "Default")
      (node (ref "SV10") (pin "27") (pinfunction "27_27") (pintype "passive"))
    )
    (net (code "167") (name "unconnected-(SV10-Pad28)") (class "Default")
      (node (ref "SV10") (pin "28") (pinfunction "28_28") (pintype "passive"))
    )
    (net (code "168") (name "unconnected-(SV10-Pad29)") (class "Default")
      (node (ref "SV10") (pin "29") (pinfunction "29_29") (pintype "passive"))
    )
    (net (code "169") (name "unconnected-(SV10-Pad30)") (class "Default")
      (node (ref "SV10") (pin "30") (pinfunction "30_30") (pintype "passive"))
    )
    (net (code "170") (name "unconnected-(SV10-Pad31)") (class "Default")
      (node (ref "SV10") (pin "31") (pinfunction "31_31") (pintype "passive"))
    )
    (net (code "171") (name "unconnected-(SV10-Pad32)") (class "Default")
      (node (ref "SV10") (pin "32") (pinfunction "32_32") (pintype "passive"))
    )
    (net (code "172") (name "unconnected-(SV10-Pad33)") (class "Default")
      (node (ref "SV10") (pin "33") (pinfunction "33_33") (pintype "passive"))
    )
    (net (code "173") (name "unconnected-(SV10-Pad34)") (class "Default")
      (node (ref "SV10") (pin "34") (pinfunction "34_34") (pintype "passive"))
    )
    (net (code "174") (name "unconnected-(SV11-Pad1)") (class "Default")
      (node (ref "SV11") (pin "1") (pinfunction "1_1") (pintype "passive"))
    )
    (net (code "175") (name "unconnected-(SV11-Pad2)") (class "Default")
      (node (ref "SV11") (pin "2") (pinfunction "2_2") (pintype "passive"))
    )
    (net (code "176") (name "unconnected-(SV11-Pad3)") (class "Default")
      (node (ref "SV11") (pin "3") (pinfunction "3_3") (pintype "passive"))
    )
    (net (code "177") (name "unconnected-(SV11-Pad4)") (class "Default")
      (node (ref "SV11") (pin "4") (pinfunction "4_4") (pintype "passive"))
    )
    (net (code "178") (name "unconnected-(SV11-Pad5)") (class "Default")
      (node (ref "SV11") (pin "5") (pinfunction "5_5") (pintype "passive"))
    )
    (net (code "179") (name "unconnected-(SV11-Pad6)") (class "Default")
      (node (ref "SV11") (pin "6") (pinfunction "6_6") (pintype "passive"))
    )
    (net (code "180") (name "unconnected-(SV11-Pad7)") (class "Default")
      (node (ref "SV11") (pin "7") (pinfunction "7_7") (pintype "passive"))
    )
    (net (code "181") (name "unconnected-(SV11-Pad8)") (class "Default")
      (node (ref "SV11") (pin "8") (pinfunction "8_8") (pintype "passive"))
    )
    (net (code "182") (name "unconnected-(SV11-Pad9)") (class "Default")
      (node (ref "SV11") (pin "9") (pinfunction "9_9") (pintype "passive"))
    )
    (net (code "183") (name "unconnected-(SV11-Pad10)") (class "Default")
      (node (ref "SV11") (pin "10") (pinfunction "10_10") (pintype "passive"))
    )
    (net (code "184") (name "unconnected-(SV11-Pad11)") (class "Default")
      (node (ref "SV11") (pin "11") (pinfunction "11_11") (pintype "passive"))
    )
    (net (code "185") (name "unconnected-(SV11-Pad12)") (class "Default")
      (node (ref "SV11") (pin "12") (pinfunction "12_12") (pintype "passive"))
    )
    (net (code "186") (name "unconnected-(SV11-Pad13)") (class "Default")
      (node (ref "SV11") (pin "13") (pinfunction "13_13") (pintype "passive"))
    )
    (net (code "187") (name "unconnected-(SV11-Pad14)") (class "Default")
      (node (ref "SV11") (pin "14") (pinfunction "14_14") (pintype "passive"))
    )
    (net (code "188") (name "unconnected-(SV11-Pad15)") (class "Default")
      (node (ref "SV11") (pin "15") (pinfunction "15_15") (pintype "passive"))
    )
    (net (code "189") (name "unconnected-(SV11-Pad16)") (class "Default")
      (node (ref "SV11") (pin "16") (pinfunction "16_16") (pintype "passive"))
    )
    (net (code "190") (name "unconnected-(SV11-Pad17)") (class "Default")
      (node (ref "SV11") (pin "17") (pinfunction "17_17") (pintype "passive"))
    )
    (net (code "191") (name "unconnected-(SV11-Pad18)") (class "Default")
      (node (ref "SV11") (pin "18") (pinfunction "18_18") (pintype "passive"))
    )
    (net (code "192") (name "unconnected-(SV11-Pad19)") (class "Default")
      (node (ref "SV11") (pin "19") (pinfunction "19_19") (pintype "passive"))
    )
    (net (code "193") (name "unconnected-(SV11-Pad20)") (class "Default")
      (node (ref "SV11") (pin "20") (pinfunction "20_20") (pintype "passive"))
    )
    (net (code "194") (name "unconnected-(SV11-Pad21)") (class "Default")
      (node (ref "SV11") (pin "21") (pinfunction "21_21") (pintype "passive"))
    )
    (net (code "195") (name "unconnected-(SV11-Pad22)") (class "Default")
      (node (ref "SV11") (pin "22") (pinfunction "22_22") (pintype "passive"))
    )
    (net (code "196") (name "unconnected-(SV11-Pad23)") (class "Default")
      (node (ref "SV11") (pin "23") (pinfunction "23_23") (pintype "passive"))
    )
    (net (code "197") (name "unconnected-(SV11-Pad24)") (class "Default")
      (node (ref "SV11") (pin "24") (pinfunction "24_24") (pintype "passive"))
    )
    (net (code "198") (name "unconnected-(SV11-Pad25)") (class "Default")
      (node (ref "SV11") (pin "25") (pinfunction "25_25") (pintype "passive"))
    )
    (net (code "199") (name "unconnected-(SV11-Pad26)") (class "Default")
      (node (ref "SV11") (pin "26") (pinfunction "26_26") (pintype "passive"))
    )
    (net (code "200") (name "unconnected-(SV11-Pad27)") (class "Default")
      (node (ref "SV11") (pin "27") (pinfunction "27_27") (pintype "passive"))
    )
    (net (code "201") (name "unconnected-(SV11-Pad28)") (class "Default")
      (node (ref "SV11") (pin "28") (pinfunction "28_28") (pintype "passive"))
    )
    (net (code "202") (name "unconnected-(SV11-Pad29)") (class "Default")
      (node (ref "SV11") (pin "29") (pinfunction "29_29") (pintype "passive"))
    )
    (net (code "203") (name "unconnected-(SV11-Pad30)") (class "Default")
      (node (ref "SV11") (pin "30") (pinfunction "30_30") (pintype "passive"))
    )
    (net (code "204") (name "unconnected-(SV11-Pad31)") (class "Default")
      (node (ref "SV11") (pin "31") (pinfunction "31_31") (pintype "passive"))
    )
    (net (code "205") (name "unconnected-(SV11-Pad32)") (class "Default")
      (node (ref "SV11") (pin "32") (pinfunction "32_32") (pintype "passive"))
    )
    (net (code "206") (name "unconnected-(SV11-Pad33)") (class "Default")
      (node (ref "SV11") (pin "33") (pinfunction "33_33") (pintype "passive"))
    )
    (net (code "207") (name "unconnected-(SV11-Pad34)") (class "Default")
      (node (ref "SV11") (pin "34") (pinfunction "34_34") (pintype "passive"))
    )
    (net (code "208") (name "unconnected-(SV12-Pad1)") (class "Default")
      (node (ref "SV12") (pin "1") (pinfunction "1_1") (pintype "passive"))
    )
    (net (code "209") (name "unconnected-(SV12-Pad2)") (class "Default")
      (node (ref "SV12") (pin "2") (pinfunction "2_2") (pintype "passive"))
    )
    (net (code "210") (name "unconnected-(SV12-Pad3)") (class "Default")
      (node (ref "SV12") (pin "3") (pinfunction "3_3") (pintype "passive"))
    )
    (net (code "211") (name "unconnected-(SV12-Pad4)") (class "Default")
      (node (ref "SV12") (pin "4") (pinfunction "4_4") (pintype "passive"))
    )
    (net (code "212") (name "unconnected-(SV12-Pad5)") (class "Default")
      (node (ref "SV12") (pin "5") (pinfunction "5_5") (pintype "passive"))
    )
    (net (code "213") (name "unconnected-(SV12-Pad6)") (class "Default")
      (node (ref "SV12") (pin "6") (pinfunction "6_6") (pintype "passive"))
    )
    (net (code "214") (name "unconnected-(SV12-Pad7)") (class "Default")
      (node (ref "SV12") (pin "7") (pinfunction "7_7") (pintype "passive"))
    )
    (net (code "215") (name "unconnected-(SV12-Pad8)") (class "Default")
      (node (ref "SV12") (pin "8") (pinfunction "8_8") (pintype "passive"))
    )
    (net (code "216") (name "unconnected-(SV12-Pad9)") (class "Default")
      (node (ref "SV12") (pin "9") (pinfunction "9_9") (pintype "passive"))
    )
    (net (code "217") (name "unconnected-(SV12-Pad10)") (class "Default")
      (node (ref "SV12") (pin "10") (pinfunction "10_10") (pintype "passive"))
    )
    (net (code "218") (name "unconnected-(SV12-Pad11)") (class "Default")
      (node (ref "SV12") (pin "11") (pinfunction "11_11") (pintype "passive"))
    )
    (net (code "219") (name "unconnected-(SV12-Pad12)") (class "Default")
      (node (ref "SV12") (pin "12") (pinfunction "12_12") (pintype "passive"))
    )
    (net (code "220") (name "unconnected-(SV12-Pad13)") (class "Default")
      (node (ref "SV12") (pin "13") (pinfunction "13_13") (pintype "passive"))
    )
    (net (code "221") (name "unconnected-(SV12-Pad14)") (class "Default")
      (node (ref "SV12") (pin "14") (pinfunction "14_14") (pintype "passive"))
    )
    (net (code "222") (name "unconnected-(SV12-Pad15)") (class "Default")
      (node (ref "SV12") (pin "15") (pinfunction "15_15") (pintype "passive"))
    )
    (net (code "223") (name "unconnected-(SV12-Pad16)") (class "Default")
      (node (ref "SV12") (pin "16") (pinfunction "16_16") (pintype "passive"))
    )
    (net (code "224") (name "unconnected-(SV12-Pad17)") (class "Default")
      (node (ref "SV12") (pin "17") (pinfunction "17_17") (pintype "passive"))
    )
    (net (code "225") (name "unconnected-(SV12-Pad18)") (class "Default")
      (node (ref "SV12") (pin "18") (pinfunction "18_18") (pintype "passive"))
    )
    (net (code "226") (name "unconnected-(SV12-Pad19)") (class "Default")
      (node (ref "SV12") (pin "19") (pinfunction "19_19") (pintype "passive"))
    )
    (net (code "227") (name "unconnected-(SV12-Pad20)") (class "Default")
      (node (ref "SV12") (pin "20") (pinfunction "20_20") (pintype "passive"))
    )
    (net (code "228") (name "unconnected-(SV12-Pad21)") (class "Default")
      (node (ref "SV12") (pin "21") (pinfunction "21_21") (pintype "passive"))
    )
    (net (code "229") (name "unconnected-(SV12-Pad22)") (class "Default")
      (node (ref "SV12") (pin "22") (pinfunction "22_22") (pintype "passive"))
    )
    (net (code "230") (name "unconnected-(SV12-Pad23)") (class "Default")
      (node (ref "SV12") (pin "23") (pinfunction "23_23") (pintype "passive"))
    )
    (net (code "231") (name "unconnected-(SV12-Pad24)") (class "Default")
      (node (ref "SV12") (pin "24") (pinfunction "24_24") (pintype "passive"))
    )
    (net (code "232") (name "unconnected-(SV12-Pad25)") (class "Default")
      (node (ref "SV12") (pin "25") (pinfunction "25_25") (pintype "passive"))
    )
    (net (code "233") (name "unconnected-(SV12-Pad26)") (class "Default")
      (node (ref "SV12") (pin "26") (pinfunction "26_26") (pintype "passive"))
    )
    (net (code "234") (name "unconnected-(SV12-Pad27)") (class "Default")
      (node (ref "SV12") (pin "27") (pinfunction "27_27") (pintype "passive"))
    )
    (net (code "235") (name "unconnected-(SV12-Pad28)") (class "Default")
      (node (ref "SV12") (pin "28") (pinfunction "28_28") (pintype "passive"))
    )
    (net (code "236") (name "unconnected-(SV12-Pad29)") (class "Default")
      (node (ref "SV12") (pin "29") (pinfunction "29_29") (pintype "passive"))
    )
    (net (code "237") (name "unconnected-(SV12-Pad30)") (class "Default")
      (node (ref "SV12") (pin "30") (pinfunction "30_30") (pintype "passive"))
    )
    (net (code "238") (name "unconnected-(SV12-Pad31)") (class "Default")
      (node (ref "SV12") (pin "31") (pinfunction "31_31") (pintype "passive"))
    )
    (net (code "239") (name "unconnected-(SV12-Pad32)") (class "Default")
      (node (ref "SV12") (pin "32") (pinfunction "32_32") (pintype "passive"))
    )
    (net (code "240") (name "unconnected-(SV12-Pad33)") (class "Default")
      (node (ref "SV12") (pin "33") (pinfunction "33_33") (pintype "passive"))
    )
    (net (code "241") (name "unconnected-(SV12-Pad34)") (class "Default")
      (node (ref "SV12") (pin "34") (pinfunction "34_34") (pintype "passive"))
    )
    (net (code "242") (name "unconnected-(SV13-Pad1)") (class "Default")
      (node (ref "SV13") (pin "1") (pinfunction "1_1") (pintype "passive"))
    )
    (net (code "243") (name "unconnected-(SV13-Pad2)") (class "Default")
      (node (ref "SV13") (pin "2") (pinfunction "2_2") (pintype "passive"))
    )
    (net (code "244") (name "unconnected-(SV13-Pad3)") (class "Default")
      (node (ref "SV13") (pin "3") (pinfunction "3_3") (pintype "passive"))
    )
    (net (code "245") (name "unconnected-(SV13-Pad4)") (class "Default")
      (node (ref "SV13") (pin "4") (pinfunction "4_4") (pintype "passive"))
    )
    (net (code "246") (name "unconnected-(SV13-Pad5)") (class "Default")
      (node (ref "SV13") (pin "5") (pinfunction "5_5") (pintype "passive"))
    )
    (net (code "247") (name "unconnected-(SV13-Pad6)") (class "Default")
      (node (ref "SV13") (pin "6") (pinfunction "6_6") (pintype "passive"))
    )
    (net (code "248") (name "unconnected-(SV13-Pad7)") (class "Default")
      (node (ref "SV13") (pin "7") (pinfunction "7_7") (pintype "passive"))
    )
    (net (code "249") (name "unconnected-(SV13-Pad8)") (class "Default")
      (node (ref "SV13") (pin "8") (pinfunction "8_8") (pintype "passive"))
    )
    (net (code "250") (name "unconnected-(SV13-Pad9)") (class "Default")
      (node (ref "SV13") (pin "9") (pinfunction "9_9") (pintype "passive"))
    )
    (net (code "251") (name "unconnected-(SV13-Pad10)") (class "Default")
      (node (ref "SV13") (pin "10") (pinfunction "10_10") (pintype "passive"))
    )
    (net (code "252") (name "unconnected-(SV13-Pad11)") (class "Default")
      (node (ref "SV13") (pin "11") (pinfunction "11_11") (pintype "passive"))
    )
    (net (code "253") (name "unconnected-(SV13-Pad12)") (class "Default")
      (node (ref "SV13") (pin "12") (pinfunction "12_12") (pintype "passive"))
    )
    (net (code "254") (name "unconnected-(SV13-Pad13)") (class "Default")
      (node (ref "SV13") (pin "13") (pinfunction "13_13") (pintype "passive"))
    )
    (net (code "255") (name "unconnected-(SV13-Pad14)") (class "Default")
      (node (ref "SV13") (pin "14") (pinfunction "14_14") (pintype "passive"))
    )
    (net (code "256") (name "unconnected-(SV13-Pad15)") (class "Default")
      (node (ref "SV13") (pin "15") (pinfunction "15_15") (pintype "passive"))
    )
    (net (code "257") (name "unconnected-(SV13-Pad16)") (class "Default")
      (node (ref "SV13") (pin "16") (pinfunction "16_16") (pintype "passive"))
    )
    (net (code "258") (name "unconnected-(SV13-Pad17)") (class "Default")
      (node (ref "SV13") (pin "17") (pinfunction "17_17") (pintype "passive"))
    )
    (net (code "259") (name "unconnected-(SV13-Pad18)") (class "Default")
      (node (ref "SV13") (pin "18") (pinfunction "18_18") (pintype "passive"))
    )
    (net (code "260") (name "unconnected-(SV13-Pad19)") (class "Default")
      (node (ref "SV13") (pin "19") (pinfunction "19_19") (pintype "passive"))
    )
    (net (code "261") (name "unconnected-(SV13-Pad20)") (class "Default")
      (node (ref "SV13") (pin "20") (pinfunction "20_20") (pintype "passive"))
    )
    (net (code "262") (name "unconnected-(SV13-Pad21)") (class "Default")
      (node (ref "SV13") (pin "21") (pinfunction "21_21") (pintype "passive"))
    )
    (net (code "263") (name "unconnected-(SV13-Pad22)") (class "Default")
      (node (ref "SV13") (pin "22") (pinfunction "22_22") (pintype "passive"))
    )
    (net (code "264") (name "unconnected-(SV13-Pad23)") (class "Default")
      (node (ref "SV13") (pin "23") (pinfunction "23_23") (pintype "passive"))
    )
    (net (code "265") (name "unconnected-(SV13-Pad24)") (class "Default")
      (node (ref "SV13") (pin "24") (pinfunction "24_24") (pintype "passive"))
    )
    (net (code "266") (name "unconnected-(SV13-Pad25)") (class "Default")
      (node (ref "SV13") (pin "25") (pinfunction "25_25") (pintype "passive"))
    )
    (net (code "267") (name "unconnected-(SV13-Pad26)") (class "Default")
      (node (ref "SV13") (pin "26") (pinfunction "26_26") (pintype "passive"))
    )
    (net (code "268") (name "unconnected-(SV13-Pad27)") (class "Default")
      (node (ref "SV13") (pin "27") (pinfunction "27_27") (pintype "passive"))
    )
    (net (code "269") (name "unconnected-(SV13-Pad28)") (class "Default")
      (node (ref "SV13") (pin "28") (pinfunction "28_28") (pintype "passive"))
    )
    (net (code "270") (name "unconnected-(SV13-Pad29)") (class "Default")
      (node (ref "SV13") (pin "29") (pinfunction "29_29") (pintype "passive"))
    )
    (net (code "271") (name "unconnected-(SV13-Pad30)") (class "Default")
      (node (ref "SV13") (pin "30") (pinfunction "30_30") (pintype "passive"))
    )
    (net (code "272") (name "unconnected-(SV13-Pad31)") (class "Default")
      (node (ref "SV13") (pin "31") (pinfunction "31_31") (pintype "passive"))
    )
    (net (code "273") (name "unconnected-(SV13-Pad32)") (class "Default")
      (node (ref "SV13") (pin "32") (pinfunction "32_32") (pintype "passive"))
    )
    (net (code "274") (name "unconnected-(SV13-Pad33)") (class "Default")
      (node (ref "SV13") (pin "33") (pinfunction "33_33") (pintype "passive"))
    )
    (net (code "275") (name "unconnected-(SV13-Pad34)") (class "Default")
      (node (ref "SV13") (pin "34") (pinfunction "34_34") (pintype "passive"))
    )
    (net (code "276") (name "unconnected-(SV14-Pad1)") (class "Default")
      (node (ref "SV14") (pin "1") (pinfunction "1_1") (pintype "passive"))
    )
    (net (code "277") (name "unconnected-(SV14-Pad2)") (class "Default")
      (node (ref "SV14") (pin "2") (pinfunction "2_2") (pintype "passive"))
    )
    (net (code "278") (name "unconnected-(SV14-Pad3)") (class "Default")
      (node (ref "SV14") (pin "3") (pinfunction "3_3") (pintype "passive"))
    )
    (net (code "279") (name "unconnected-(SV14-Pad4)") (class "Default")
      (node (ref "SV14") (pin "4") (pinfunction "4_4") (pintype "passive"))
    )
    (net (code "280") (name "unconnected-(SV14-Pad5)") (class "Default")
      (node (ref "SV14") (pin "5") (pinfunction "5_5") (pintype "passive"))
    )
    (net (code "281") (name "unconnected-(SV14-Pad6)") (class "Default")
      (node (ref "SV14") (pin "6") (pinfunction "6_6") (pintype "passive"))
    )
    (net (code "282") (name "unconnected-(SV14-Pad7)") (class "Default")
      (node (ref "SV14") (pin "7") (pinfunction "7_7") (pintype "passive"))
    )
    (net (code "283") (name "unconnected-(SV14-Pad8)") (class "Default")
      (node (ref "SV14") (pin "8") (pinfunction "8_8") (pintype "passive"))
    )
    (net (code "284") (name "unconnected-(SV14-Pad9)") (class "Default")
      (node (ref "SV14") (pin "9") (pinfunction "9_9") (pintype "passive"))
    )
    (net (code "285") (name "unconnected-(SV14-Pad10)") (class "Default")
      (node (ref "SV14") (pin "10") (pinfunction "10_10") (pintype "passive"))
    )
    (net (code "286") (name "unconnected-(SV14-Pad11)") (class "Default")
      (node (ref "SV14") (pin "11") (pinfunction "11_11") (pintype "passive"))
    )
    (net (code "287") (name "unconnected-(SV14-Pad12)") (class "Default")
      (node (ref "SV14") (pin "12") (pinfunction "12_12") (pintype "passive"))
    )
    (net (code "288") (name "unconnected-(SV14-Pad13)") (class "Default")
      (node (ref "SV14") (pin "13") (pinfunction "13_13") (pintype "passive"))
    )
    (net (code "289") (name "unconnected-(SV14-Pad14)") (class "Default")
      (node (ref "SV14") (pin "14") (pinfunction "14_14") (pintype "passive"))
    )
    (net (code "290") (name "unconnected-(SV14-Pad15)") (class "Default")
      (node (ref "SV14") (pin "15") (pinfunction "15_15") (pintype "passive"))
    )
    (net (code "291") (name "unconnected-(SV14-Pad16)") (class "Default")
      (node (ref "SV14") (pin "16") (pinfunction "16_16") (pintype "passive"))
    )
    (net (code "292") (name "unconnected-(SV14-Pad17)") (class "Default")
      (node (ref "SV14") (pin "17") (pinfunction "17_17") (pintype "passive"))
    )
    (net (code "293") (name "unconnected-(SV14-Pad18)") (class "Default")
      (node (ref "SV14") (pin "18") (pinfunction "18_18") (pintype "passive"))
    )
    (net (code "294") (name "unconnected-(SV14-Pad19)") (class "Default")
      (node (ref "SV14") (pin "19") (pinfunction "19_19") (pintype "passive"))
    )
    (net (code "295") (name "unconnected-(SV14-Pad20)") (class "Default")
      (node (ref "SV14") (pin "20") (pinfunction "20_20") (pintype "passive"))
    )
    (net (code "296") (name "unconnected-(SV14-Pad21)") (class "Default")
      (node (ref "SV14") (pin "21") (pinfunction "21_21") (pintype "passive"))
    )
    (net (code "297") (name "unconnected-(SV14-Pad22)") (class "Default")
      (node (ref "SV14") (pin "22") (pinfunction "22_22") (pintype "passive"))
    )
    (net (code "298") (name "unconnected-(SV14-Pad23)") (class "Default")
      (node (ref "SV14") (pin "23") (pinfunction "23_23") (pintype "passive"))
    )
    (net (code "299") (name "unconnected-(SV14-Pad24)") (class "Default")
      (node (ref "SV14") (pin "24") (pinfunction "24_24") (pintype "passive"))
    )
    (net (code "300") (name "unconnected-(SV14-Pad25)") (class "Default")
      (node (ref "SV14") (pin "25") (pinfunction "25_25") (pintype "passive"))
    )
    (net (code "301") (name "unconnected-(SV14-Pad26)") (class "Default")
      (node (ref "SV14") (pin "26") (pinfunction "26_26") (pintype "passive"))
    )
    (net (code "302") (name "unconnected-(SV14-Pad27)") (class "Default")
      (node (ref "SV14") (pin "27") (pinfunction "27_27") (pintype "passive"))
    )
    (net (code "303") (name "unconnected-(SV14-Pad28)") (class "Default")
      (node (ref "SV14") (pin "28") (pinfunction "28_28") (pintype "passive"))
    )
    (net (code "304") (name "unconnected-(SV14-Pad29)") (class "Default")
      (node (ref "SV14") (pin "29") (pinfunction "29_29") (pintype "passive"))
    )
    (net (code "305") (name "unconnected-(SV14-Pad30)") (class "Default")
      (node (ref "SV14") (pin "30") (pinfunction "30_30") (pintype "passive"))
    )
    (net (code "306") (name "unconnected-(SV14-Pad31)") (class "Default")
      (node (ref "SV14") (pin "31") (pinfunction "31_31") (pintype "passive"))
    )
    (net (code "307") (name "unconnected-(SV14-Pad32)") (class "Default")
      (node (ref "SV14") (pin "32") (pinfunction "32_32") (pintype "passive"))
    )
    (net (code "308") (name "unconnected-(SV14-Pad33)") (class "Default")
      (node (ref "SV14") (pin "33") (pinfunction "33_33") (pintype "passive"))
    )
    (net (code "309") (name "unconnected-(SV14-Pad34)") (class "Default")
      (node (ref "SV14") (pin "34") (pinfunction "34_34") (pintype "passive"))
    )
    (net (code "310") (name "unconnected-(SV15-Pad1)") (class "Default")
      (node (ref "SV15") (pin "1") (pinfunction "1_1") (pintype "passive"))
    )
    (net (code "311") (name "unconnected-(SV15-Pad2)") (class "Default")
      (node (ref "SV15") (pin "2") (pinfunction "2_2") (pintype "passive"))
    )
    (net (code "312") (name "unconnected-(SV15-Pad3)") (class "Default")
      (node (ref "SV15") (pin "3") (pinfunction "3_3") (pintype "passive"))
    )
    (net (code "313") (name "unconnected-(SV15-Pad4)") (class "Default")
      (node (ref "SV15") (pin "4") (pinfunction "4_4") (pintype "passive"))
    )
    (net (code "314") (name "unconnected-(SV15-Pad5)") (class "Default")
      (node (ref "SV15") (pin "5") (pinfunction "5_5") (pintype "passive"))
    )
    (net (code "315") (name "unconnected-(SV15-Pad6)") (class "Default")
      (node (ref "SV15") (pin "6") (pinfunction "6_6") (pintype "passive"))
    )
    (net (code "316") (name "unconnected-(SV15-Pad7)") (class "Default")
      (node (ref "SV15") (pin "7") (pinfunction "7_7") (pintype "passive"))
    )
    (net (code "317") (name "unconnected-(SV15-Pad8)") (class "Default")
      (node (ref "SV15") (pin "8") (pinfunction "8_8") (pintype "passive"))
    )
    (net (code "318") (name "unconnected-(SV15-Pad9)") (class "Default")
      (node (ref "SV15") (pin "9") (pinfunction "9_9") (pintype "passive"))
    )
    (net (code "319") (name "unconnected-(SV15-Pad10)") (class "Default")
      (node (ref "SV15") (pin "10") (pinfunction "10_10") (pintype "passive"))
    )
    (net (code "320") (name "unconnected-(SV15-Pad11)") (class "Default")
      (node (ref "SV15") (pin "11") (pinfunction "11_11") (pintype "passive"))
    )
    (net (code "321") (name "unconnected-(SV15-Pad12)") (class "Default")
      (node (ref "SV15") (pin "12") (pinfunction "12_12") (pintype "passive"))
    )
    (net (code "322") (name "unconnected-(SV15-Pad13)") (class "Default")
      (node (ref "SV15") (pin "13") (pinfunction "13_13") (pintype "passive"))
    )
    (net (code "323") (name "unconnected-(SV15-Pad14)") (class "Default")
      (node (ref "SV15") (pin "14") (pinfunction "14_14") (pintype "passive"))
    )
    (net (code "324") (name "unconnected-(SV15-Pad15)") (class "Default")
      (node (ref "SV15") (pin "15") (pinfunction "15_15") (pintype "passive"))
    )
    (net (code "325") (name "unconnected-(SV15-Pad16)") (class "Default")
      (node (ref "SV15") (pin "16") (pinfunction "16_16") (pintype "passive"))
    )
    (net (code "326") (name "unconnected-(SV15-Pad17)") (class "Default")
      (node (ref "SV15") (pin "17") (pinfunction "17_17") (pintype "passive"))
    )
    (net (code "327") (name "unconnected-(SV15-Pad18)") (class "Default")
      (node (ref "SV15") (pin "18") (pinfunction "18_18") (pintype "passive"))
    )
    (net (code "328") (name "unconnected-(SV15-Pad19)") (class "Default")
      (node (ref "SV15") (pin "19") (pinfunction "19_19") (pintype "passive"))
    )
    (net (code "329") (name "unconnected-(SV15-Pad20)") (class "Default")
      (node (ref "SV15") (pin "20") (pinfunction "20_20") (pintype "passive"))
    )
    (net (code "330") (name "unconnected-(SV15-Pad21)") (class "Default")
      (node (ref "SV15") (pin "21") (pinfunction "21_21") (pintype "passive"))
    )
    (net (code "331") (name "unconnected-(SV15-Pad22)") (class "Default")
      (node (ref "SV15") (pin "22") (pinfunction "22_22") (pintype "passive"))
    )
    (net (code "332") (name "unconnected-(SV15-Pad23)") (class "Default")
      (node (ref "SV15") (pin "23") (pinfunction "23_23") (pintype "passive"))
    )
    (net (code "333") (name "unconnected-(SV15-Pad24)") (class "Default")
      (node (ref "SV15") (pin "24") (pinfunction "24_24") (pintype "passive"))
    )
    (net (code "334") (name "unconnected-(SV15-Pad25)") (class "Default")
      (node (ref "SV15") (pin "25") (pinfunction "25_25") (pintype "passive"))
    )
    (net (code "335") (name "unconnected-(SV15-Pad26)") (class "Default")
      (node (ref "SV15") (pin "26") (pinfunction "26_26") (pintype "passive"))
    )
    (net (code "336") (name "unconnected-(SV15-Pad27)") (class "Default")
      (node (ref "SV15") (pin "27") (pinfunction "27_27") (pintype "passive"))
    )
    (net (code "337") (name "unconnected-(SV15-Pad28)") (class "Default")
      (node (ref "SV15") (pin "28") (pinfunction "28_28") (pintype "passive"))
    )
    (net (code "338") (name "unconnected-(SV15-Pad29)") (class "Default")
      (node (ref "SV15") (pin "29") (pinfunction "29_29") (pintype "passive"))
    )
    (net (code "339") (name "unconnected-(SV15-Pad30)") (class "Default")
      (node (ref "SV15") (pin "30") (pinfunction "30_30") (pintype "passive"))
    )
    (net (code "340") (name "unconnected-(SV15-Pad31)") (class "Default")
      (node (ref "SV15") (pin "31") (pinfunction "31_31") (pintype "passive"))
    )
    (net (code "341") (name "unconnected-(SV15-Pad32)") (class "Default")
      (node (ref "SV15") (pin "32") (pinfunction "32_32") (pintype "passive"))
    )
    (net (code "342") (name "unconnected-(SV15-Pad33)") (class "Default")
      (node (ref "SV15") (pin "33") (pinfunction "33_33") (pintype "passive"))
    )
    (net (code "343") (name "unconnected-(SV15-Pad34)") (class "Default")
      (node (ref "SV15") (pin "34") (pinfunction "34_34") (pintype "passive"))
    )
    (net (code "344") (name "unconnected-(SV16-Pad1)") (class "Default")
      (node (ref "SV16") (pin "1") (pinfunction "1_1") (pintype "passive"))
    )
    (net (code "345") (name "unconnected-(SV16-Pad2)") (class "Default")
      (node (ref "SV16") (pin "2") (pinfunction "2_2") (pintype "passive"))
    )
    (net (code "346") (name "unconnected-(SV16-Pad3)") (class "Default")
      (node (ref "SV16") (pin "3") (pinfunction "3_3") (pintype "passive"))
    )
    (net (code "347") (name "unconnected-(SV16-Pad4)") (class "Default")
      (node (ref "SV16") (pin "4") (pinfunction "4_4") (pintype "passive"))
    )
    (net (code "348") (name "unconnected-(SV16-Pad5)") (class "Default")
      (node (ref "SV16") (pin "5") (pinfunction "5_5") (pintype "passive"))
    )
    (net (code "349") (name "unconnected-(SV16-Pad6)") (class "Default")
      (node (ref "SV16") (pin "6") (pinfunction "6_6") (pintype "passive"))
    )
    (net (code "350") (name "unconnected-(SV16-Pad7)") (class "Default")
      (node (ref "SV16") (pin "7") (pinfunction "7_7") (pintype "passive"))
    )
    (net (code "351") (name "unconnected-(SV16-Pad8)") (class "Default")
      (node (ref "SV16") (pin "8") (pinfunction "8_8") (pintype "passive"))
    )
    (net (code "352") (name "unconnected-(SV16-Pad9)") (class "Default")
      (node (ref "SV16") (pin "9") (pinfunction "9_9") (pintype "passive"))
    )
    (net (code "353") (name "unconnected-(SV16-Pad10)") (class "Default")
      (node (ref "SV16") (pin "10") (pinfunction "10_10") (pintype "passive"))
    )
    (net (code "354") (name "unconnected-(SV16-Pad11)") (class "Default")
      (node (ref "SV16") (pin "11") (pinfunction "11_11") (pintype "passive"))
    )
    (net (code "355") (name "unconnected-(SV16-Pad12)") (class "Default")
      (node (ref "SV16") (pin "12") (pinfunction "12_12") (pintype "passive"))
    )
    (net (code "356") (name "unconnected-(SV16-Pad13)") (class "Default")
      (node (ref "SV16") (pin "13") (pinfunction "13_13") (pintype "passive"))
    )
    (net (code "357") (name "unconnected-(SV16-Pad14)") (class "Default")
      (node (ref "SV16") (pin "14") (pinfunction "14_14") (pintype "passive"))
    )
    (net (code "358") (name "unconnected-(SV16-Pad15)") (class "Default")
      (node (ref "SV16") (pin "15") (pinfunction "15_15") (pintype "passive"))
    )
    (net (code "359") (name "unconnected-(SV16-Pad16)") (class "Default")
      (node (ref "SV16") (pin "16") (pinfunction "16_16") (pintype "passive"))
    )
    (net (code "360") (name "unconnected-(SV16-Pad17)") (class "Default")
      (node (ref "SV16") (pin "17") (pinfunction "17_17") (pintype "passive"))
    )
    (net (code "361") (name "unconnected-(SV16-Pad18)") (class "Default")
      (node (ref "SV16") (pin "18") (pinfunction "18_18") (pintype "passive"))
    )
    (net (code "362") (name "unconnected-(SV16-Pad19)") (class "Default")
      (node (ref "SV16") (pin "19") (pinfunction "19_19") (pintype "passive"))
    )
    (net (code "363") (name "unconnected-(SV16-Pad20)") (class "Default")
      (node (ref "SV16") (pin "20") (pinfunction "20_20") (pintype "passive"))
    )
    (net (code "364") (name "unconnected-(SV16-Pad21)") (class "Default")
      (node (ref "SV16") (pin "21") (pinfunction "21_21") (pintype "passive"))
    )
    (net (code "365") (name "unconnected-(SV16-Pad22)") (class "Default")
      (node (ref "SV16") (pin "22") (pinfunction "22_22") (pintype "passive"))
    )
    (net (code "366") (name "unconnected-(SV16-Pad23)") (class "Default")
      (node (ref "SV16") (pin "23") (pinfunction "23_23") (pintype "passive"))
    )
    (net (code "367") (name "unconnected-(SV16-Pad24)") (class "Default")
      (node (ref "SV16") (pin "24") (pinfunction "24_24") (pintype "passive"))
    )
    (net (code "368") (name "unconnected-(SV16-Pad25)") (class "Default")
      (node (ref "SV16") (pin "25") (pinfunction "25_25") (pintype "passive"))
    )
    (net (code "369") (name "unconnected-(SV16-Pad26)") (class "Default")
      (node (ref "SV16") (pin "26") (pinfunction "26_26") (pintype "passive"))
    )
    (net (code "370") (name "unconnected-(SV16-Pad27)") (class "Default")
      (node (ref "SV16") (pin "27") (pinfunction "27_27") (pintype "passive"))
    )
    (net (code "371") (name "unconnected-(SV16-Pad28)") (class "Default")
      (node (ref "SV16") (pin "28") (pinfunction "28_28") (pintype "passive"))
    )
    (net (code "372") (name "unconnected-(SV16-Pad29)") (class "Default")
      (node (ref "SV16") (pin "29") (pinfunction "29_29") (pintype "passive"))
    )
    (net (code "373") (name "unconnected-(SV16-Pad30)") (class "Default")
      (node (ref "SV16") (pin "30") (pinfunction "30_30") (pintype "passive"))
    )
    (net (code "374") (name "unconnected-(SV16-Pad31)") (class "Default")
      (node (ref "SV16") (pin "31") (pinfunction "31_31") (pintype "passive"))
    )
    (net (code "375") (name "unconnected-(SV16-Pad32)") (class "Default")
      (node (ref "SV16") (pin "32") (pinfunction "32_32") (pintype "passive"))
    )
    (net (code "376") (name "unconnected-(SV16-Pad33)") (class "Default")
      (node (ref "SV16") (pin "33") (pinfunction "33_33") (pintype "passive"))
    )
    (net (code "377") (name "unconnected-(SV16-Pad34)") (class "Default")
      (node (ref "SV16") (pin "34") (pinfunction "34_34") (pintype "passive"))
    )
    (net (code "378") (name "unconnected-(SV17-Pad1)") (class "Default")
      (node (ref "SV17") (pin "1") (pinfunction "1_1") (pintype "passive"))
    )
    (net (code "379") (name "unconnected-(SV17-Pad2)") (class "Default")
      (node (ref "SV17") (pin "2") (pinfunction "2_2") (pintype "passive"))
    )
    (net (code "380") (name "unconnected-(SV17-Pad3)") (class "Default")
      (node (ref "SV17") (pin "3") (pinfunction "3_3") (pintype "passive"))
    )
    (net (code "381") (name "unconnected-(SV17-Pad4)") (class "Default")
      (node (ref "SV17") (pin "4") (pinfunction "4_4") (pintype "passive"))
    )
    (net (code "382") (name "unconnected-(SV17-Pad5)") (class "Default")
      (node (ref "SV17") (pin "5") (pinfunction "5_5") (pintype "passive"))
    )
    (net (code "383") (name "unconnected-(SV17-Pad6)") (class "Default")
      (node (ref "SV17") (pin "6") (pinfunction "6_6") (pintype "passive"))
    )
    (net (code "384") (name "unconnected-(SV17-Pad7)") (class "Default")
      (node (ref "SV17") (pin "7") (pinfunction "7_7") (pintype "passive"))
    )
    (net (code "385") (name "unconnected-(SV17-Pad8)") (class "Default")
      (node (ref "SV17") (pin "8") (pinfunction "8_8") (pintype "passive"))
    )
    (net (code "386") (name "unconnected-(SV17-Pad9)") (class "Default")
      (node (ref "SV17") (pin "9") (pinfunction "9_9") (pintype "passive"))
    )
    (net (code "387") (name "unconnected-(SV17-Pad10)") (class "Default")
      (node (ref "SV17") (pin "10") (pinfunction "10_10") (pintype "passive"))
    )
    (net (code "388") (name "unconnected-(SV17-Pad11)") (class "Default")
      (node (ref "SV17") (pin "11") (pinfunction "11_11") (pintype "passive"))
    )
    (net (code "389") (name "unconnected-(SV17-Pad12)") (class "Default")
      (node (ref "SV17") (pin "12") (pinfunction "12_12") (pintype "passive"))
    )
    (net (code "390") (name "unconnected-(SV17-Pad13)") (class "Default")
      (node (ref "SV17") (pin "13") (pinfunction "13_13") (pintype "passive"))
    )
    (net (code "391") (name "unconnected-(SV17-Pad14)") (class "Default")
      (node (ref "SV17") (pin "14") (pinfunction "14_14") (pintype "passive"))
    )
    (net (code "392") (name "unconnected-(SV17-Pad15)") (class "Default")
      (node (ref "SV17") (pin "15") (pinfunction "15_15") (pintype "passive"))
    )
    (net (code "393") (name "unconnected-(SV17-Pad16)") (class "Default")
      (node (ref "SV17") (pin "16") (pinfunction "16_16") (pintype "passive"))
    )
    (net (code "394") (name "unconnected-(SV17-Pad17)") (class "Default")
      (node (ref "SV17") (pin "17") (pinfunction "17_17") (pintype "passive"))
    )
    (net (code "395") (name "unconnected-(SV17-Pad18)") (class "Default")
      (node (ref "SV17") (pin "18") (pinfunction "18_18") (pintype "passive"))
    )
    (net (code "396") (name "unconnected-(SV17-Pad19)") (class "Default")
      (node (ref "SV17") (pin "19") (pinfunction "19_19") (pintype "passive"))
    )
    (net (code "397") (name "unconnected-(SV17-Pad20)") (class "Default")
      (node (ref "SV17") (pin "20") (pinfunction "20_20") (pintype "passive"))
    )
    (net (code "398") (name "unconnected-(SV17-Pad21)") (class "Default")
      (node (ref "SV17") (pin "21") (pinfunction "21_21") (pintype "passive"))
    )
    (net (code "399") (name "unconnected-(SV17-Pad22)") (class "Default")
      (node (ref "SV17") (pin "22") (pinfunction "22_22") (pintype "passive"))
    )
    (net (code "400") (name "unconnected-(SV17-Pad23)") (class "Default")
      (node (ref "SV17") (pin "23") (pinfunction "23_23") (pintype "passive"))
    )
    (net (code "401") (name "unconnected-(SV17-Pad24)") (class "Default")
      (node (ref "SV17") (pin "24") (pinfunction "24_24") (pintype "passive"))
    )
    (net (code "402") (name "unconnected-(SV17-Pad25)") (class "Default")
      (node (ref "SV17") (pin "25") (pinfunction "25_25") (pintype "passive"))
    )
    (net (code "403") (name "unconnected-(SV17-Pad26)") (class "Default")
      (node (ref "SV17") (pin "26") (pinfunction "26_26") (pintype "passive"))
    )
    (net (code "404") (name "unconnected-(SV17-Pad27)") (class "Default")
      (node (ref "SV17") (pin "27") (pinfunction "27_27") (pintype "passive"))
    )
    (net (code "405") (name "unconnected-(SV17-Pad28)") (class "Default")
      (node (ref "SV17") (pin "28") (pinfunction "28_28") (pintype "passive"))
    )
    (net (code "406") (name "unconnected-(SV17-Pad29)") (class "Default")
      (node (ref "SV17") (pin "29") (pinfunction "29_29") (pintype "passive"))
    )
    (net (code "407") (name "unconnected-(SV17-Pad30)") (class "Default")
      (node (ref "SV17") (pin "30") (pinfunction "30_30") (pintype "passive"))
    )
    (net (code "408") (name "unconnected-(SV17-Pad31)") (class "Default")
      (node (ref "SV17") (pin "31") (pinfunction "31_31") (pintype "passive"))
    )
    (net (code "409") (name "unconnected-(SV17-Pad32)") (class "Default")
      (node (ref "SV17") (pin "32") (pinfunction "32_32") (pintype "passive"))
    )
    (net (code "410") (name "unconnected-(SV17-Pad33)") (class "Default")
      (node (ref "SV17") (pin "33") (pinfunction "33_33") (pintype "passive"))
    )
    (net (code "411") (name "unconnected-(SV17-Pad34)") (class "Default")
      (node (ref "SV17") (pin "34") (pinfunction "34_34") (pintype "passive"))
    )
    (net (code "412") (name "unconnected-(SV18-Pad1)") (class "Default")
      (node (ref "SV18") (pin "1") (pinfunction "1_1") (pintype "passive"))
    )
    (net (code "413") (name "unconnected-(SV18-Pad2)") (class "Default")
      (node (ref "SV18") (pin "2") (pinfunction "2_2") (pintype "passive"))
    )
    (net (code "414") (name "unconnected-(SV18-Pad3)") (class "Default")
      (node (ref "SV18") (pin "3") (pinfunction "3_3") (pintype "passive"))
    )
    (net (code "415") (name "unconnected-(SV18-Pad4)") (class "Default")
      (node (ref "SV18") (pin "4") (pinfunction "4_4") (pintype "passive"))
    )
    (net (code "416") (name "unconnected-(SV18-Pad5)") (class "Default")
      (node (ref "SV18") (pin "5") (pinfunction "5_5") (pintype "passive"))
    )
    (net (code "417") (name "unconnected-(SV18-Pad6)") (class "Default")
      (node (ref "SV18") (pin "6") (pinfunction "6_6") (pintype "passive"))
    )
    (net (code "418") (name "unconnected-(SV18-Pad7)") (class "Default")
      (node (ref "SV18") (pin "7") (pinfunction "7_7") (pintype "passive"))
    )
    (net (code "419") (name "unconnected-(SV18-Pad8)") (class "Default")
      (node (ref "SV18") (pin "8") (pinfunction "8_8") (pintype "passive"))
    )
    (net (code "420") (name "unconnected-(SV18-Pad9)") (class "Default")
      (node (ref "SV18") (pin "9") (pinfunction "9_9") (pintype "passive"))
    )
    (net (code "421") (name "unconnected-(SV18-Pad10)") (class "Default")
      (node (ref "SV18") (pin "10") (pinfunction "10_10") (pintype "passive"))
    )
    (net (code "422") (name "unconnected-(SV18-Pad11)") (class "Default")
      (node (ref "SV18") (pin "11") (pinfunction "11_11") (pintype "passive"))
    )
    (net (code "423") (name "unconnected-(SV18-Pad12)") (class "Default")
      (node (ref "SV18") (pin "12") (pinfunction "12_12") (pintype "passive"))
    )
    (net (code "424") (name "unconnected-(SV18-Pad13)") (class "Default")
      (node (ref "SV18") (pin "13") (pinfunction "13_13") (pintype "passive"))
    )
    (net (code "425") (name "unconnected-(SV18-Pad14)") (class "Default")
      (node (ref "SV18") (pin "14") (pinfunction "14_14") (pintype "passive"))
    )
    (net (code "426") (name "unconnected-(SV18-Pad15)") (class "Default")
      (node (ref "SV18") (pin "15") (pinfunction "15_15") (pintype "passive"))
    )
    (net (code "427") (name "unconnected-(SV18-Pad16)") (class "Default")
      (node (ref "SV18") (pin "16") (pinfunction "16_16") (pintype "passive"))
    )
    (net (code "428") (name "unconnected-(SV18-Pad17)") (class "Default")
      (node (ref "SV18") (pin "17") (pinfunction "17_17") (pintype "passive"))
    )
    (net (code "429") (name "unconnected-(SV18-Pad18)") (class "Default")
      (node (ref "SV18") (pin "18") (pinfunction "18_18") (pintype "passive"))
    )
    (net (code "430") (name "unconnected-(SV18-Pad19)") (class "Default")
      (node (ref "SV18") (pin "19") (pinfunction "19_19") (pintype "passive"))
    )
    (net (code "431") (name "unconnected-(SV18-Pad20)") (class "Default")
      (node (ref "SV18") (pin "20") (pinfunction "20_20") (pintype "passive"))
    )
    (net (code "432") (name "unconnected-(SV18-Pad21)") (class "Default")
      (node (ref "SV18") (pin "21") (pinfunction "21_21") (pintype "passive"))
    )
    (net (code "433") (name "unconnected-(SV18-Pad22)") (class "Default")
      (node (ref "SV18") (pin "22") (pinfunction "22_22") (pintype "passive"))
    )
    (net (code "434") (name "unconnected-(SV18-Pad23)") (class "Default")
      (node (ref "SV18") (pin "23") (pinfunction "23_23") (pintype "passive"))
    )
    (net (code "435") (name "unconnected-(SV18-Pad24)") (class "Default")
      (node (ref "SV18") (pin "24") (pinfunction "24_24") (pintype "passive"))
    )
    (net (code "436") (name "unconnected-(SV18-Pad25)") (class "Default")
      (node (ref "SV18") (pin "25") (pinfunction "25_25") (pintype "passive"))
    )
    (net (code "437") (name "unconnected-(SV18-Pad26)") (class "Default")
      (node (ref "SV18") (pin "26") (pinfunction "26_26") (pintype "passive"))
    )
    (net (code "438") (name "unconnected-(SV18-Pad27)") (class "Default")
      (node (ref "SV18") (pin "27") (pinfunction "27_27") (pintype "passive"))
    )
    (net (code "439") (name "unconnected-(SV18-Pad28)") (class "Default")
      (node (ref "SV18") (pin "28") (pinfunction "28_28") (pintype "passive"))
    )
    (net (code "440") (name "unconnected-(SV18-Pad29)") (class "Default")
      (node (ref "SV18") (pin "29") (pinfunction "29_29") (pintype "passive"))
    )
    (net (code "441") (name "unconnected-(SV18-Pad30)") (class "Default")
      (node (ref "SV18") (pin "30") (pinfunction "30_30") (pintype "passive"))
    )
    (net (code "442") (name "unconnected-(SV18-Pad31)") (class "Default")
      (node (ref "SV18") (pin "31") (pinfunction "31_31") (pintype "passive"))
    )
    (net (code "443") (name "unconnected-(SV18-Pad32)") (class "Default")
      (node (ref "SV18") (pin "32") (pinfunction "32_32") (pintype "passive"))
    )
    (net (code "444") (name "unconnected-(SV18-Pad33)") (class "Default")
      (node (ref "SV18") (pin "33") (pinfunction "33_33") (pintype "passive"))
    )
    (net (code "445") (name "unconnected-(SV18-Pad34)") (class "Default")
      (node (ref "SV18") (pin "34") (pinfunction "34_34") (pintype "passive"))
    )
  )
)
